# atmega328p_PCB_schematic.net
KiCad netlist of a schematic drawn in EAGLE
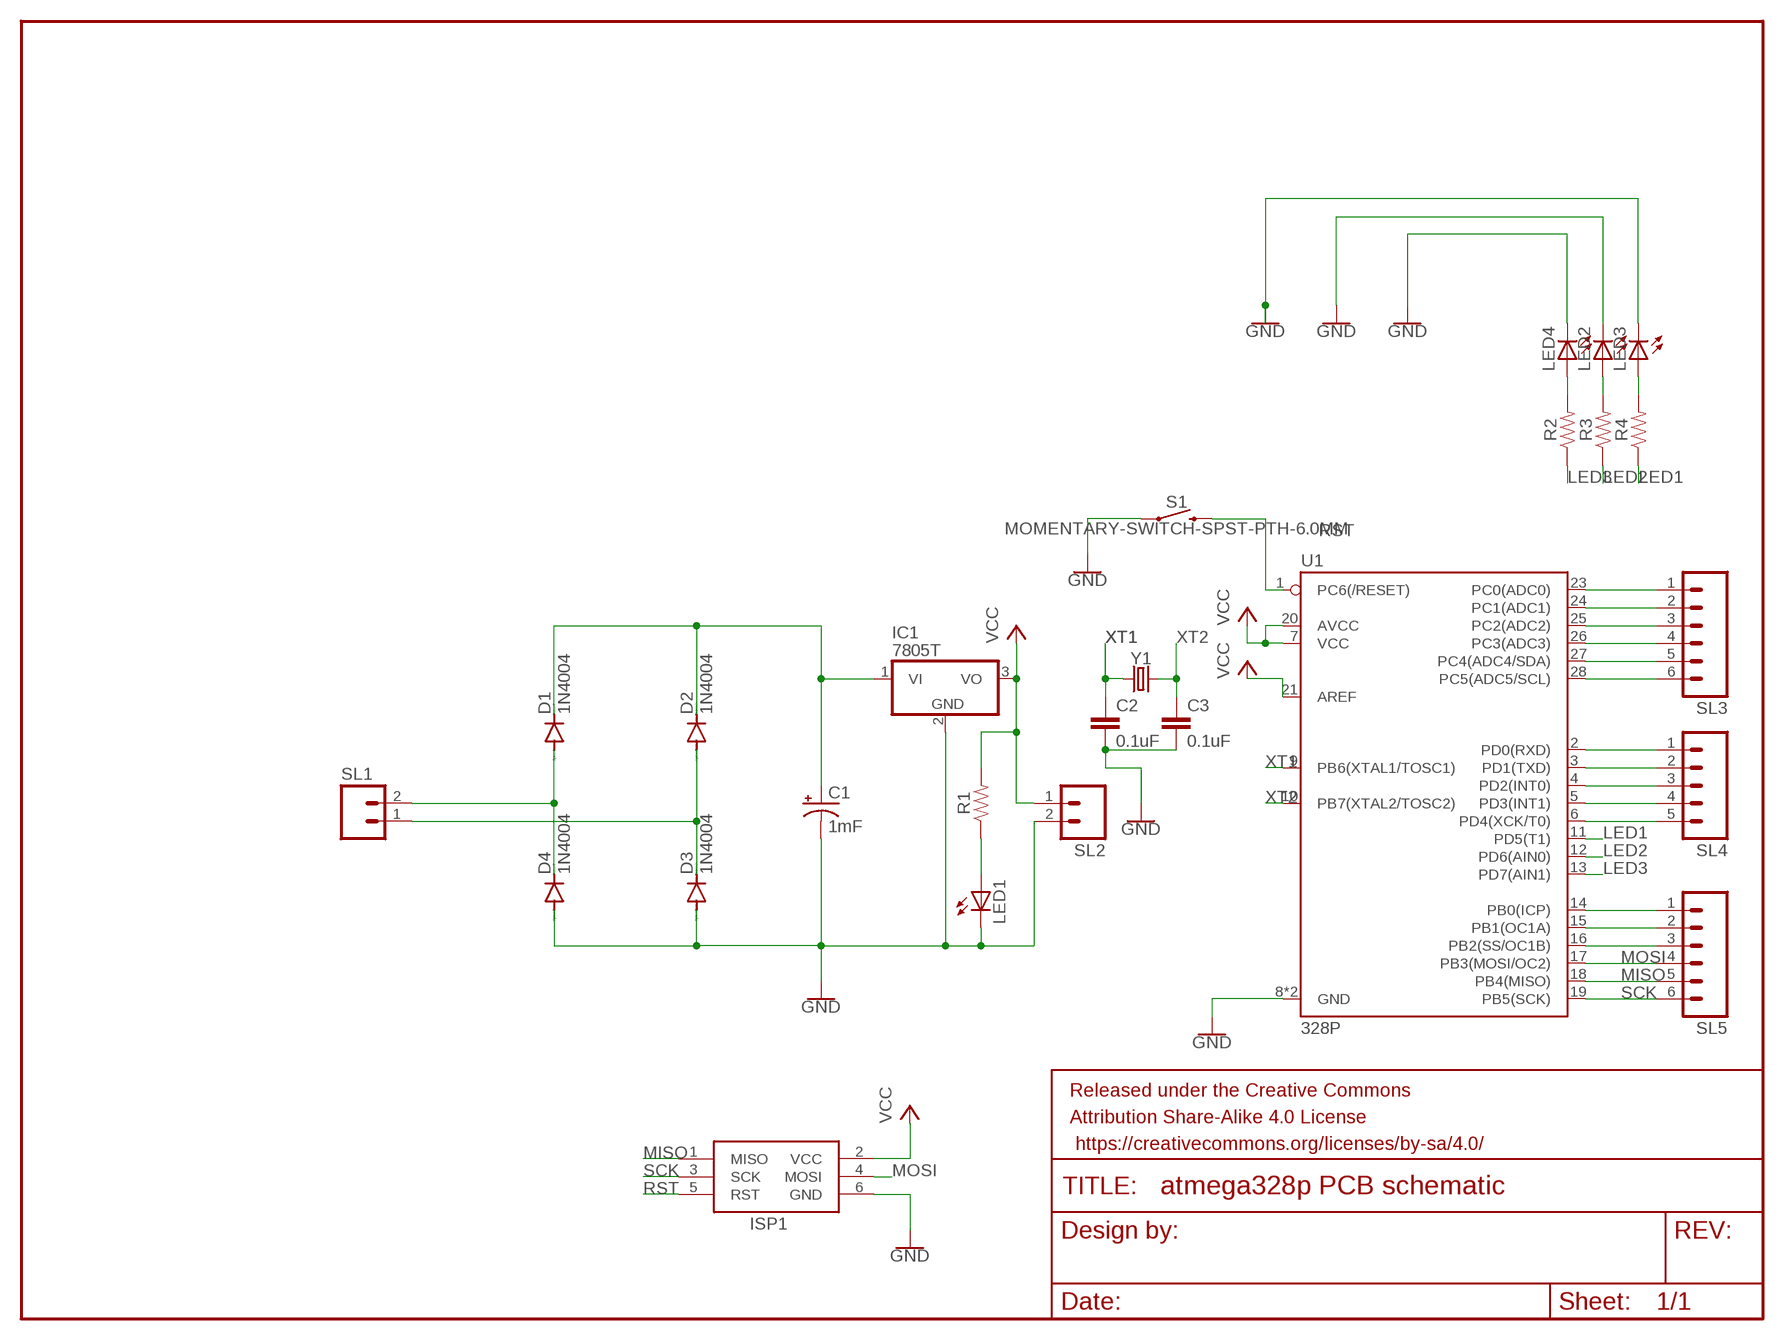
[diagram p0: schematic, sheet 1]

(export (version "E")
  (design (tool "Eeschema 10.0.6"))
  (components
    (comp (ref "C1")
      (value "1mF")
      (footprint "eagle-import:CPOL-RADIAL-5MM-10MM")
      (libsource (lib "eagle-import") (part "1000UF-RADIAL-5MM-25V-20%"))
    )
    (comp (ref "C2")
      (value "0.1uF")
      (footprint "eagle-import:CAP-PTH-SMALL-KIT")
      (libsource (lib "eagle-import") (part "0.1UF-KIT-EZ-50V-20%"))
    )
    (comp (ref "C3")
      (value "0.1uF")
      (footprint "eagle-import:CAP-PTH-SMALL-KIT")
      (libsource (lib "eagle-import") (part "0.1UF-KIT-EZ-50V-20%"))
    )
    (comp (ref "D1")
      (value "1N4004")
      (footprint "eagle-import:DO41-10")
      (libsource (lib "eagle-import") (part "1N4004"))
    )
    (comp (ref "D2")
      (value "1N4004")
      (footprint "eagle-import:DO41-10")
      (libsource (lib "eagle-import") (part "1N4004"))
    )
    (comp (ref "D3")
      (value "1N4004")
      (footprint "eagle-import:DO41-10")
      (libsource (lib "eagle-import") (part "1N4004"))
    )
    (comp (ref "D4")
      (value "1N4004")
      (footprint "eagle-import:DO41-10")
      (libsource (lib "eagle-import") (part "1N4004"))
    )
    (comp (ref "FRAME1")
      (value "FRAME-LETTERNO_PACKAGE")
      (footprint "eagle-import:DUMMY")
      (fields (field (name "DESIGNER") "Nobody"))
      (libsource (lib "eagle-import") (part "FRAME-LETTERNO_PACKAGE"))
    )
    (comp (ref "IC1")
      (value "7805T")
      (footprint "eagle-import:TO220H")
      (libsource (lib "eagle-import") (part "78T05"))
    )
    (comp (ref "ISP1")
      (value "AVRISP-6")
      (footprint "eagle-import:AVRISP")
      (libsource (lib "eagle-import") (part "AVRISP-6"))
    )
    (comp (ref "LED1")
      (value "LED5MM")
      (footprint "eagle-import:LED5MM")
      (libsource (lib "eagle-import") (part "LED5MM"))
    )
    (comp (ref "LED2")
      (value "LED3MM")
      (footprint "eagle-import:LED3MM")
      (libsource (lib "eagle-import") (part "LED3MM"))
    )
    (comp (ref "LED3")
      (value "LED3MM")
      (footprint "eagle-import:LED3MM")
      (libsource (lib "eagle-import") (part "LED3MM"))
    )
    (comp (ref "LED4")
      (value "LED3MM")
      (footprint "eagle-import:LED3MM")
      (libsource (lib "eagle-import") (part "LED3MM"))
    )
    (comp (ref "R1")
      (value "RESISTORAXIAL-0.3")
      (footprint "eagle-import:AXIAL-0.3")
      (libsource (lib "eagle-import") (part "RESISTORAXIAL-0.3"))
    )
    (comp (ref "R2")
      (value "RESISTORAXIAL-0.3")
      (footprint "eagle-import:AXIAL-0.3")
      (libsource (lib "eagle-import") (part "RESISTORAXIAL-0.3"))
    )
    (comp (ref "R3")
      (value "RESISTORAXIAL-0.3")
      (footprint "eagle-import:AXIAL-0.3")
      (libsource (lib "eagle-import") (part "RESISTORAXIAL-0.3"))
    )
    (comp (ref "R4")
      (value "RESISTORAXIAL-0.3")
      (footprint "eagle-import:AXIAL-0.3")
      (libsource (lib "eagle-import") (part "RESISTORAXIAL-0.3"))
    )
    (comp (ref "S1")
      (value "MOMENTARY-SWITCH-SPST-PTH-6.0MM")
      (footprint "eagle-import:TACTILE_SWITCH_PTH_6.0MM")
      (libsource (lib "eagle-import") (part "MOMENTARY-SWITCH-SPST-PTH-6.0MM"))
    )
    (comp (ref "SL1")
      (value "M02")
      (footprint "eagle-import:02P")
      (libsource (lib "eagle-import") (part "M02"))
    )
    (comp (ref "SL2")
      (value "M02")
      (footprint "eagle-import:02P")
      (libsource (lib "eagle-import") (part "M02"))
    )
    (comp (ref "SL3")
      (value "M06")
      (footprint "eagle-import:06P")
      (libsource (lib "eagle-import") (part "M06"))
    )
    (comp (ref "SL4")
      (value "M05")
      (footprint "eagle-import:05P")
      (libsource (lib "eagle-import") (part "M05"))
    )
    (comp (ref "SL5")
      (value "M06")
      (footprint "eagle-import:06P")
      (libsource (lib "eagle-import") (part "M06"))
    )
    (comp (ref "U1")
      (value "328P")
      (footprint "eagle-import:DIP28")
      (libsource (lib "eagle-import") (part "ATMEGA328P_PDIP"))
    )
    (comp (ref "Y1")
      (value "CRYSTALPTH-HC49US")
      (footprint "eagle-import:HC49US")
      (libsource (lib "eagle-import") (part "CRYSTALPTH-HC49US"))
    )
  )
  (nets
    (net (code "1") (name "/LED1") (class "Default")
      (node (ref "R4") (pin "P$1") (pinfunction "1_P$1") (pintype "passive"))
      (node (ref "U1") (pin "11") (pinfunction "PD5(T1)_11") (pintype "bidirectional"))
    )
    (net (code "2") (name "/LED2") (class "Default")
      (node (ref "R3") (pin "P$1") (pinfunction "1_P$1") (pintype "passive"))
      (node (ref "U1") (pin "12") (pinfunction "PD6(AIN0)_12") (pintype "bidirectional"))
    )
    (net (code "3") (name "/LED3") (class "Default")
      (node (ref "R2") (pin "P$1") (pinfunction "1_P$1") (pintype "passive"))
      (node (ref "U1") (pin "13") (pinfunction "PD7(AIN1)_13") (pintype "bidirectional"))
    )
    (net (code "4") (name "/MISO") (class "Default")
      (node (ref "ISP1") (pin "1") (pinfunction "MISO_1") (pintype "input"))
      (node (ref "SL5") (pin "5") (pinfunction "5_5") (pintype "passive"))
      (node (ref "U1") (pin "18") (pinfunction "PB4(MISO)_18") (pintype "bidirectional"))
    )
    (net (code "5") (name "/MOSI") (class "Default")
      (node (ref "ISP1") (pin "4") (pinfunction "MOSI_4") (pintype "output"))
      (node (ref "SL5") (pin "4") (pinfunction "4_4") (pintype "passive"))
      (node (ref "U1") (pin "17") (pinfunction "PB3(MOSI/OC2)_17") (pintype "bidirectional"))
    )
    (net (code "6") (name "/RST") (class "Default")
      (node (ref "ISP1") (pin "5") (pinfunction "RST_5") (pintype "output"))
      (node (ref "S1") (pin "3") (pinfunction "2_3") (pintype "passive"))
      (node (ref "U1") (pin "1") (pinfunction "PC6(/RESET)_1") (pintype "bidirectional"))
    )
    (net (code "7") (name "/SCK") (class "Default")
      (node (ref "ISP1") (pin "3") (pinfunction "SCK_3") (pintype "output"))
      (node (ref "SL5") (pin "6") (pinfunction "6_6") (pintype "passive"))
      (node (ref "U1") (pin "19") (pinfunction "PB5(SCK)_19") (pintype "bidirectional"))
    )
    (net (code "8") (name "/XT1") (class "Default")
      (node (ref "C2") (pin "1") (pinfunction "1_1") (pintype "passive"))
      (node (ref "U1") (pin "9") (pinfunction "PB6(XTAL1/TOSC1)_9") (pintype "bidirectional"))
      (node (ref "Y1") (pin "1") (pinfunction "1_1") (pintype "passive"))
    )
    (net (code "9") (name "/XT2") (class "Default")
      (node (ref "C3") (pin "1") (pinfunction "1_1") (pintype "passive"))
      (node (ref "U1") (pin "10") (pinfunction "PB7(XTAL2/TOSC2)_10") (pintype "bidirectional"))
      (node (ref "Y1") (pin "2") (pinfunction "2_2") (pintype "passive"))
    )
    (net (code "10") (name "GND") (class "Default")
      (node (ref "C1") (pin "-") (pinfunction "-_-") (pintype "passive"))
      (node (ref "C2") (pin "2") (pinfunction "2_2") (pintype "passive"))
      (node (ref "C3") (pin "2") (pinfunction "2_2") (pintype "passive"))
      (node (ref "D3") (pin "A") (pinfunction "A_A") (pintype "passive"))
      (node (ref "D4") (pin "A") (pinfunction "A_A") (pintype "passive"))
      (node (ref "IC1") (pin "2") (pinfunction "GND_2") (pintype "passive"))
      (node (ref "ISP1") (pin "6") (pinfunction "GND_6") (pintype "power_in"))
      (node (ref "LED1") (pin "K") (pinfunction "C_K") (pintype "passive"))
      (node (ref "LED2") (pin "K") (pinfunction "C_K") (pintype "passive"))
      (node (ref "LED3") (pin "K") (pinfunction "C_K") (pintype "passive"))
      (node (ref "LED4") (pin "K") (pinfunction "C_K") (pintype "passive"))
      (node (ref "S1") (pin "1") (pinfunction "1_1") (pintype "passive"))
      (node (ref "SL2") (pin "2") (pinfunction "2_2") (pintype "passive"))
      (node (ref "U1") (pin "22") (pinfunction "GND_22") (pintype "bidirectional"))
      (node (ref "U1") (pin "8") (pinfunction "GND_8") (pintype "bidirectional"))
    )
    (net (code "11") (name "Net-(D1-PadA)") (class "Default")
      (node (ref "D1") (pin "A") (pinfunction "A_A") (pintype "passive"))
      (node (ref "D4") (pin "C") (pinfunction "C_C") (pintype "passive"))
      (node (ref "SL1") (pin "2") (pinfunction "2_2") (pintype "passive"))
    )
    (net (code "12") (name "Net-(D2-PadA)") (class "Default")
      (node (ref "D2") (pin "A") (pinfunction "A_A") (pintype "passive"))
      (node (ref "D3") (pin "C") (pinfunction "C_C") (pintype "passive"))
      (node (ref "SL1") (pin "1") (pinfunction "1_1") (pintype "passive"))
    )
    (net (code "13") (name "Net-(IC1-VI)") (class "Default")
      (node (ref "C1") (pin "+") (pinfunction "+_+") (pintype "passive"))
      (node (ref "D1") (pin "C") (pinfunction "C_C") (pintype "passive"))
      (node (ref "D2") (pin "C") (pinfunction "C_C") (pintype "passive"))
      (node (ref "IC1") (pin "1") (pinfunction "VI_1") (pintype "input"))
    )
    (net (code "14") (name "Net-(R1-1)") (class "Default")
      (node (ref "LED1") (pin "A") (pinfunction "A_A") (pintype "passive"))
      (node (ref "R1") (pin "P$1") (pinfunction "1_P$1") (pintype "passive"))
    )
    (net (code "15") (name "Net-(R2-2)") (class "Default")
      (node (ref "LED4") (pin "A") (pinfunction "A_A") (pintype "passive"))
      (node (ref "R2") (pin "P$2") (pinfunction "2_P$2") (pintype "passive"))
    )
    (net (code "16") (name "Net-(R3-2)") (class "Default")
      (node (ref "LED2") (pin "A") (pinfunction "A_A") (pintype "passive"))
      (node (ref "R3") (pin "P$2") (pinfunction "2_P$2") (pintype "passive"))
    )
    (net (code "17") (name "Net-(R4-2)") (class "Default")
      (node (ref "LED3") (pin "A") (pinfunction "A_A") (pintype "passive"))
      (node (ref "R4") (pin "P$2") (pinfunction "2_P$2") (pintype "passive"))
    )
    (net (code "18") (name "Net-(U1-PB0(ICP))") (class "Default")
      (node (ref "SL5") (pin "1") (pinfunction "1_1") (pintype "passive"))
      (node (ref "U1") (pin "14") (pinfunction "PB0(ICP)_14") (pintype "bidirectional"))
    )
    (net (code "19") (name "Net-(U1-PB1(OC1A))") (class "Default")
      (node (ref "SL5") (pin "2") (pinfunction "2_2") (pintype "passive"))
      (node (ref "U1") (pin "15") (pinfunction "PB1(OC1A)_15") (pintype "bidirectional"))
    )
    (net (code "20") (name "Net-(U1-PB2(SS{slash}OC1B))") (class "Default")
      (node (ref "SL5") (pin "3") (pinfunction "3_3") (pintype "passive"))
      (node (ref "U1") (pin "16") (pinfunction "PB2(SS/OC1B)_16") (pintype "bidirectional"))
    )
    (net (code "21") (name "Net-(U1-PC0(ADC0))") (class "Default")
      (node (ref "SL3") (pin "1") (pinfunction "1_1") (pintype "passive"))
      (node (ref "U1") (pin "23") (pinfunction "PC0(ADC0)_23") (pintype "bidirectional"))
    )
    (net (code "22") (name "Net-(U1-PC1(ADC1))") (class "Default")
      (node (ref "SL3") (pin "2") (pinfunction "2_2") (pintype "passive"))
      (node (ref "U1") (pin "24") (pinfunction "PC1(ADC1)_24") (pintype "bidirectional"))
    )
    (net (code "23") (name "Net-(U1-PC2(ADC2))") (class "Default")
      (node (ref "SL3") (pin "3") (pinfunction "3_3") (pintype "passive"))
      (node (ref "U1") (pin "25") (pinfunction "PC2(ADC2)_25") (pintype "bidirectional"))
    )
    (net (code "24") (name "Net-(U1-PC3(ADC3))") (class "Default")
      (node (ref "SL3") (pin "4") (pinfunction "4_4") (pintype "passive"))
      (node (ref "U1") (pin "26") (pinfunction "PC3(ADC3)_26") (pintype "bidirectional"))
    )
    (net (code "25") (name "Net-(U1-PC4(ADC4{slash}SDA))") (class "Default")
      (node (ref "SL3") (pin "5") (pinfunction "5_5") (pintype "passive"))
      (node (ref "U1") (pin "27") (pinfunction "PC4(ADC4/SDA)_27") (pintype "bidirectional"))
    )
    (net (code "26") (name "Net-(U1-PC5(ADC5{slash}SCL))") (class "Default")
      (node (ref "SL3") (pin "6") (pinfunction "6_6") (pintype "passive"))
      (node (ref "U1") (pin "28") (pinfunction "PC5(ADC5/SCL)_28") (pintype "bidirectional"))
    )
    (net (code "27") (name "Net-(U1-PD0(RXD))") (class "Default")
      (node (ref "SL4") (pin "1") (pinfunction "1_1") (pintype "passive"))
      (node (ref "U1") (pin "2") (pinfunction "PD0(RXD)_2") (pintype "bidirectional"))
    )
    (net (code "28") (name "Net-(U1-PD1(TXD))") (class "Default")
      (node (ref "SL4") (pin "2") (pinfunction "2_2") (pintype "passive"))
      (node (ref "U1") (pin "3") (pinfunction "PD1(TXD)_3") (pintype "bidirectional"))
    )
    (net (code "29") (name "Net-(U1-PD2(INT0))") (class "Default")
      (node (ref "SL4") (pin "3") (pinfunction "3_3") (pintype "passive"))
      (node (ref "U1") (pin "4") (pinfunction "PD2(INT0)_4") (pintype "bidirectional"))
    )
    (net (code "30") (name "Net-(U1-PD3(INT1))") (class "Default")
      (node (ref "SL4") (pin "4") (pinfunction "4_4") (pintype "passive"))
      (node (ref "U1") (pin "5") (pinfunction "PD3(INT1)_5") (pintype "bidirectional"))
    )
    (net (code "31") (name "Net-(U1-PD4(XCK{slash}T0))") (class "Default")
      (node (ref "SL4") (pin "5") (pinfunction "5_5") (pintype "passive"))
      (node (ref "U1") (pin "6") (pinfunction "PD4(XCK/T0)_6") (pintype "bidirectional"))
    )
    (net (code "32") (name "VCC") (class "Default")
      (node (ref "IC1") (pin "3") (pinfunction "VO_3") (pintype "passive"))
      (node (ref "ISP1") (pin "2") (pinfunction "VCC_2") (pintype "power_in"))
      (node (ref "R1") (pin "P$2") (pinfunction "2_P$2") (pintype "passive"))
      (node (ref "SL2") (pin "1") (pinfunction "1_1") (pintype "passive"))
      (node (ref "U1") (pin "20") (pinfunction "AVCC_20") (pintype "bidirectional"))
      (node (ref "U1") (pin "21") (pinfunction "AREF_21") (pintype "bidirectional"))
      (node (ref "U1") (pin "7") (pinfunction "VCC_7") (pintype "bidirectional"))
    )
  )
)
